# RS9113-XXX-X1X_Breakout.net
KiCad netlist of a schematic drawn in EAGLE
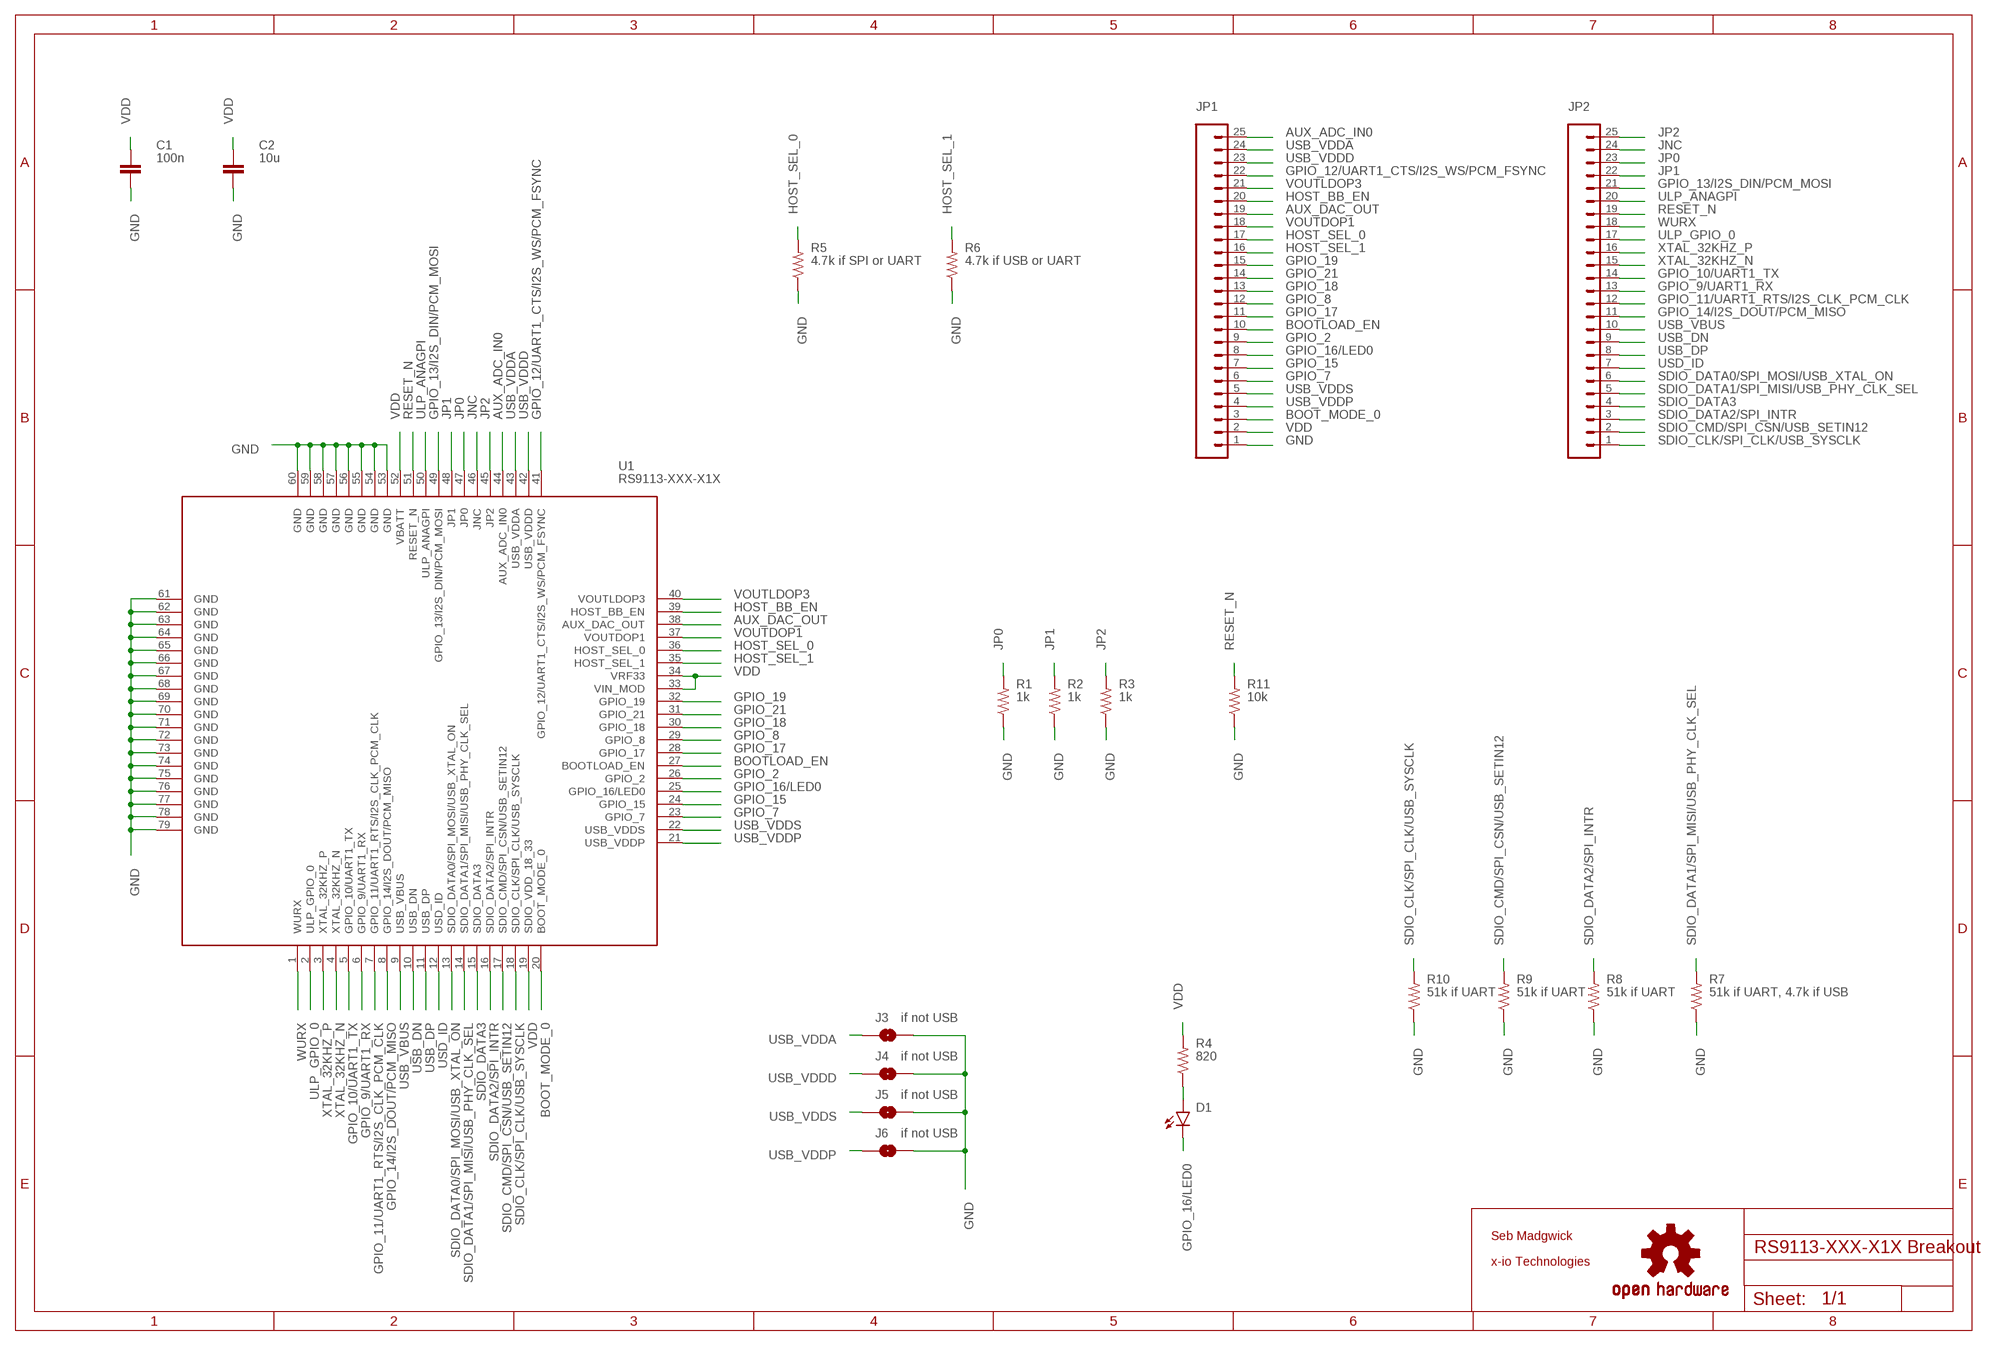
[diagram p0: schematic, sheet 1]

(export (version "E")
  (design (tool "Eeschema 10.0.6"))
  (components
    (comp (ref "C1")
      (value "100n")
      (footprint "eagle-import:0603-CAP")
      (libsource (lib "eagle-import") (part "CAP0603-CAP"))
    )
    (comp (ref "C2")
      (value "10u")
      (footprint "eagle-import:0603-CAP")
      (libsource (lib "eagle-import") (part "CAP0603-CAP"))
    )
    (comp (ref "D1")
      (value "GREEN")
      (footprint "eagle-import:LED-0603")
      (libsource (lib "eagle-import") (part "LED-GREEN0603"))
    )
    (comp (ref "J3")
      (value "if not USB")
      (footprint "eagle-import:SJ_2S-NO")
      (libsource (lib "eagle-import") (part "SOLDERJUMPERNO"))
    )
    (comp (ref "J4")
      (value "if not USB")
      (footprint "eagle-import:SJ_2S-NO")
      (libsource (lib "eagle-import") (part "SOLDERJUMPERNO"))
    )
    (comp (ref "J5")
      (value "if not USB")
      (footprint "eagle-import:SJ_2S-NO")
      (libsource (lib "eagle-import") (part "SOLDERJUMPERNO"))
    )
    (comp (ref "J6")
      (value "if not USB")
      (footprint "eagle-import:SJ_2S-NO")
      (libsource (lib "eagle-import") (part "SOLDERJUMPERNO"))
    )
    (comp (ref "JP1")
      (value "M25PTH")
      (footprint "eagle-import:1X25")
      (libsource (lib "eagle-import") (part "M25PTH"))
    )
    (comp (ref "JP2")
      (value "M25PTH")
      (footprint "eagle-import:1X25")
      (libsource (lib "eagle-import") (part "M25PTH"))
    )
    (comp (ref "LOGO1")
      (value "OSHW-LOGOS")
      (footprint "eagle-import:OSHW-LOGO-S")
      (libsource (lib "eagle-import") (part "OSHW-LOGOS"))
    )
    (comp (ref "R1")
      (value "1k")
      (footprint "eagle-import:0603-RES")
      (libsource (lib "eagle-import") (part "RESISTOR0603"))
    )
    (comp (ref "R2")
      (value "1k")
      (footprint "eagle-import:0603-RES")
      (libsource (lib "eagle-import") (part "RESISTOR0603"))
    )
    (comp (ref "R3")
      (value "1k")
      (footprint "eagle-import:0603-RES")
      (libsource (lib "eagle-import") (part "RESISTOR0603"))
    )
    (comp (ref "R4")
      (value "820")
      (footprint "eagle-import:0603-RES")
      (libsource (lib "eagle-import") (part "RESISTOR0603"))
    )
    (comp (ref "R5")
      (value "4.7k if SPI or UART")
      (footprint "eagle-import:0603-RES")
      (libsource (lib "eagle-import") (part "RESISTOR0603"))
    )
    (comp (ref "R6")
      (value "4.7k if USB or UART")
      (footprint "eagle-import:0603-RES")
      (libsource (lib "eagle-import") (part "RESISTOR0603"))
    )
    (comp (ref "R7")
      (value "51k if UART, 4.7k if USB")
      (footprint "eagle-import:0603-RES")
      (libsource (lib "eagle-import") (part "RESISTOR0603"))
    )
    (comp (ref "R8")
      (value "51k if UART")
      (footprint "eagle-import:0603-RES")
      (libsource (lib "eagle-import") (part "RESISTOR0603"))
    )
    (comp (ref "R9")
      (value "51k if UART")
      (footprint "eagle-import:0603-RES")
      (libsource (lib "eagle-import") (part "RESISTOR0603"))
    )
    (comp (ref "R10")
      (value "51k if UART")
      (footprint "eagle-import:0603-RES")
      (libsource (lib "eagle-import") (part "RESISTOR0603"))
    )
    (comp (ref "R11")
      (value "10k")
      (footprint "eagle-import:0603-RES")
      (libsource (lib "eagle-import") (part "RESISTOR0603"))
    )
    (comp (ref "U1")
      (value "RS9113-XXX-X1X")
      (footprint "eagle-import:RS9113-XXX-X1X")
      (libsource (lib "eagle-import") (part "RS9113-XXX-X1X"))
    )
  )
  (nets
    (net (code "1") (name "/AUX_ADC_IN0") (class "Default")
      (node (ref "JP1") (pin "25") (pinfunction "25_25") (pintype "passive"))
      (node (ref "U1") (pin "44") (pinfunction "AUX_ADC_IN0_44") (pintype "bidirectional"))
    )
    (net (code "2") (name "/AUX_DAC_OUT") (class "Default")
      (node (ref "JP1") (pin "19") (pinfunction "19_19") (pintype "passive"))
      (node (ref "U1") (pin "38") (pinfunction "AUX_DAC_OUT_38") (pintype "bidirectional"))
    )
    (net (code "3") (name "/BOOTLOAD_EN") (class "Default")
      (node (ref "JP1") (pin "10") (pinfunction "10_10") (pintype "passive"))
      (node (ref "U1") (pin "27") (pinfunction "BOOTLOAD_EN_27") (pintype "bidirectional"))
    )
    (net (code "4") (name "/BOOT_MODE_0") (class "Default")
      (node (ref "JP1") (pin "3") (pinfunction "3_3") (pintype "passive"))
      (node (ref "U1") (pin "20") (pinfunction "BOOT_MODE_0_20") (pintype "bidirectional"))
    )
    (net (code "5") (name "/GND") (class "Default")
      (node (ref "C1") (pin "2") (pinfunction "2_2") (pintype "passive"))
      (node (ref "C2") (pin "2") (pinfunction "2_2") (pintype "passive"))
      (node (ref "J3") (pin "1") (pinfunction "1_1") (pintype "passive"))
      (node (ref "J4") (pin "1") (pinfunction "1_1") (pintype "passive"))
      (node (ref "J5") (pin "1") (pinfunction "1_1") (pintype "passive"))
      (node (ref "J6") (pin "1") (pinfunction "1_1") (pintype "passive"))
      (node (ref "JP1") (pin "1") (pinfunction "1_1") (pintype "passive"))
      (node (ref "R1") (pin "1") (pinfunction "1_1") (pintype "passive"))
      (node (ref "R10") (pin "1") (pinfunction "1_1") (pintype "passive"))
      (node (ref "R11") (pin "1") (pinfunction "1_1") (pintype "passive"))
      (node (ref "R2") (pin "1") (pinfunction "1_1") (pintype "passive"))
      (node (ref "R3") (pin "1") (pinfunction "1_1") (pintype "passive"))
      (node (ref "R5") (pin "1") (pinfunction "1_1") (pintype "passive"))
      (node (ref "R6") (pin "1") (pinfunction "1_1") (pintype "passive"))
      (node (ref "R7") (pin "1") (pinfunction "1_1") (pintype "passive"))
      (node (ref "R8") (pin "1") (pinfunction "1_1") (pintype "passive"))
      (node (ref "R9") (pin "1") (pinfunction "1_1") (pintype "passive"))
      (node (ref "U1") (pin "53") (pinfunction "GND_53") (pintype "bidirectional"))
      (node (ref "U1") (pin "54") (pinfunction "GND_54") (pintype "bidirectional"))
      (node (ref "U1") (pin "55") (pinfunction "GND_55") (pintype "bidirectional"))
      (node (ref "U1") (pin "56") (pinfunction "GND_56") (pintype "bidirectional"))
      (node (ref "U1") (pin "57") (pinfunction "GND_57") (pintype "bidirectional"))
      (node (ref "U1") (pin "58") (pinfunction "GND_58") (pintype "bidirectional"))
      (node (ref "U1") (pin "59") (pinfunction "GND_59") (pintype "bidirectional"))
      (node (ref "U1") (pin "60") (pinfunction "GND_60") (pintype "bidirectional"))
      (node (ref "U1") (pin "61") (pinfunction "GND_61") (pintype "bidirectional"))
      (node (ref "U1") (pin "62") (pinfunction "GND_62") (pintype "bidirectional"))
      (node (ref "U1") (pin "63") (pinfunction "GND_63") (pintype "bidirectional"))
      (node (ref "U1") (pin "64") (pinfunction "GND_64") (pintype "bidirectional"))
      (node (ref "U1") (pin "65") (pinfunction "GND_65") (pintype "bidirectional"))
      (node (ref "U1") (pin "66") (pinfunction "GND_66") (pintype "bidirectional"))
      (node (ref "U1") (pin "67") (pinfunction "GND_67") (pintype "bidirectional"))
      (node (ref "U1") (pin "68") (pinfunction "GND_68") (pintype "bidirectional"))
      (node (ref "U1") (pin "69") (pinfunction "GND_69") (pintype "bidirectional"))
      (node (ref "U1") (pin "70") (pinfunction "GND_70") (pintype "bidirectional"))
      (node (ref "U1") (pin "71") (pinfunction "GND_71") (pintype "bidirectional"))
      (node (ref "U1") (pin "72") (pinfunction "GND_72") (pintype "bidirectional"))
      (node (ref "U1") (pin "73") (pinfunction "GND_73") (pintype "bidirectional"))
      (node (ref "U1") (pin "74") (pinfunction "GND_74") (pintype "bidirectional"))
      (node (ref "U1") (pin "75") (pinfunction "GND_75") (pintype "bidirectional"))
      (node (ref "U1") (pin "76") (pinfunction "GND_76") (pintype "bidirectional"))
      (node (ref "U1") (pin "77") (pinfunction "GND_77") (pintype "bidirectional"))
      (node (ref "U1") (pin "78") (pinfunction "GND_78") (pintype "bidirectional"))
      (node (ref "U1") (pin "79") (pinfunction "GND_79") (pintype "bidirectional"))
    )
    (net (code "6") (name "/GPIO_2") (class "Default")
      (node (ref "JP1") (pin "9") (pinfunction "9_9") (pintype "passive"))
      (node (ref "U1") (pin "26") (pinfunction "GPIO_2_26") (pintype "bidirectional"))
    )
    (net (code "7") (name "/GPIO_7") (class "Default")
      (node (ref "JP1") (pin "6") (pinfunction "6_6") (pintype "passive"))
      (node (ref "U1") (pin "23") (pinfunction "GPIO_7_23") (pintype "bidirectional"))
    )
    (net (code "8") (name "/GPIO_8") (class "Default")
      (node (ref "JP1") (pin "12") (pinfunction "12_12") (pintype "passive"))
      (node (ref "U1") (pin "29") (pinfunction "GPIO_8_29") (pintype "bidirectional"))
    )
    (net (code "9") (name "/GPIO_9{slash}UART1_RX") (class "Default")
      (node (ref "JP2") (pin "13") (pinfunction "13_13") (pintype "passive"))
      (node (ref "U1") (pin "6") (pinfunction "GPIO_9/UART1_RX_6") (pintype "bidirectional"))
    )
    (net (code "10") (name "/GPIO_10{slash}UART1_TX") (class "Default")
      (node (ref "JP2") (pin "14") (pinfunction "14_14") (pintype "passive"))
      (node (ref "U1") (pin "5") (pinfunction "GPIO_10/UART1_TX_5") (pintype "bidirectional"))
    )
    (net (code "11") (name "/GPIO_11{slash}UART1_RTS{slash}I2S_CLK_PCM_CLK") (class "Default")
      (node (ref "JP2") (pin "12") (pinfunction "12_12") (pintype "passive"))
      (node (ref "U1") (pin "7") (pinfunction "GPIO_11/UART1_RTS/I2S_CLK_PCM_CLK_7") (pintype "bidirectional"))
    )
    (net (code "12") (name "/GPIO_12{slash}UART1_CTS{slash}I2S_WS{slash}PCM_FSYNC") (class "Default")
      (node (ref "JP1") (pin "22") (pinfunction "22_22") (pintype "passive"))
      (node (ref "U1") (pin "41") (pinfunction "GPIO_12/UART1_CTS/I2S_WS/PCM_FSYNC_41") (pintype "bidirectional"))
    )
    (net (code "13") (name "/GPIO_13{slash}I2S_DIN{slash}PCM_MOSI") (class "Default")
      (node (ref "JP2") (pin "21") (pinfunction "21_21") (pintype "passive"))
      (node (ref "U1") (pin "49") (pinfunction "GPIO_13/I2S_DIN/PCM_MOSI_49") (pintype "bidirectional"))
    )
    (net (code "14") (name "/GPIO_14{slash}I2S_DOUT{slash}PCM_MISO") (class "Default")
      (node (ref "JP2") (pin "11") (pinfunction "11_11") (pintype "passive"))
      (node (ref "U1") (pin "8") (pinfunction "GPIO_14/I2S_DOUT/PCM_MISO_8") (pintype "bidirectional"))
    )
    (net (code "15") (name "/GPIO_15") (class "Default")
      (node (ref "JP1") (pin "7") (pinfunction "7_7") (pintype "passive"))
      (node (ref "U1") (pin "24") (pinfunction "GPIO_15_24") (pintype "bidirectional"))
    )
    (net (code "16") (name "/GPIO_16{slash}LED0") (class "Default")
      (node (ref "D1") (pin "C") (pinfunction "C_C") (pintype "passive"))
      (node (ref "JP1") (pin "8") (pinfunction "8_8") (pintype "passive"))
      (node (ref "U1") (pin "25") (pinfunction "GPIO_16/LED0_25") (pintype "bidirectional"))
    )
    (net (code "17") (name "/GPIO_17") (class "Default")
      (node (ref "JP1") (pin "11") (pinfunction "11_11") (pintype "passive"))
      (node (ref "U1") (pin "28") (pinfunction "GPIO_17_28") (pintype "bidirectional"))
    )
    (net (code "18") (name "/GPIO_18") (class "Default")
      (node (ref "JP1") (pin "13") (pinfunction "13_13") (pintype "passive"))
      (node (ref "U1") (pin "30") (pinfunction "GPIO_18_30") (pintype "bidirectional"))
    )
    (net (code "19") (name "/GPIO_19") (class "Default")
      (node (ref "JP1") (pin "15") (pinfunction "15_15") (pintype "passive"))
      (node (ref "U1") (pin "32") (pinfunction "GPIO_19_32") (pintype "bidirectional"))
    )
    (net (code "20") (name "/GPIO_21") (class "Default")
      (node (ref "JP1") (pin "14") (pinfunction "14_14") (pintype "passive"))
      (node (ref "U1") (pin "31") (pinfunction "GPIO_21_31") (pintype "bidirectional"))
    )
    (net (code "21") (name "/HOST_BB_EN") (class "Default")
      (node (ref "JP1") (pin "20") (pinfunction "20_20") (pintype "passive"))
      (node (ref "U1") (pin "39") (pinfunction "HOST_BB_EN_39") (pintype "bidirectional"))
    )
    (net (code "22") (name "/HOST_SEL_0") (class "Default")
      (node (ref "JP1") (pin "17") (pinfunction "17_17") (pintype "passive"))
      (node (ref "R5") (pin "2") (pinfunction "2_2") (pintype "passive"))
      (node (ref "U1") (pin "36") (pinfunction "HOST_SEL_0_36") (pintype "bidirectional"))
    )
    (net (code "23") (name "/HOST_SEL_1") (class "Default")
      (node (ref "JP1") (pin "16") (pinfunction "16_16") (pintype "passive"))
      (node (ref "R6") (pin "2") (pinfunction "2_2") (pintype "passive"))
      (node (ref "U1") (pin "35") (pinfunction "HOST_SEL_1_35") (pintype "bidirectional"))
    )
    (net (code "24") (name "/JNC") (class "Default")
      (node (ref "JP2") (pin "24") (pinfunction "24_24") (pintype "passive"))
      (node (ref "U1") (pin "46") (pinfunction "JNC_46") (pintype "bidirectional"))
    )
    (net (code "25") (name "/JP0") (class "Default")
      (node (ref "JP2") (pin "23") (pinfunction "23_23") (pintype "passive"))
      (node (ref "R1") (pin "2") (pinfunction "2_2") (pintype "passive"))
      (node (ref "U1") (pin "47") (pinfunction "JP0_47") (pintype "bidirectional"))
    )
    (net (code "26") (name "/JP1") (class "Default")
      (node (ref "JP2") (pin "22") (pinfunction "22_22") (pintype "passive"))
      (node (ref "R2") (pin "2") (pinfunction "2_2") (pintype "passive"))
      (node (ref "U1") (pin "48") (pinfunction "JP1_48") (pintype "bidirectional"))
    )
    (net (code "27") (name "/JP2") (class "Default")
      (node (ref "JP2") (pin "25") (pinfunction "25_25") (pintype "passive"))
      (node (ref "R3") (pin "2") (pinfunction "2_2") (pintype "passive"))
      (node (ref "U1") (pin "45") (pinfunction "JP2_45") (pintype "bidirectional"))
    )
    (net (code "28") (name "/RESET_N") (class "Default")
      (node (ref "JP2") (pin "19") (pinfunction "19_19") (pintype "passive"))
      (node (ref "R11") (pin "2") (pinfunction "2_2") (pintype "passive"))
      (node (ref "U1") (pin "51") (pinfunction "RESET_N_51") (pintype "bidirectional"))
    )
    (net (code "29") (name "/SDIO_CLK{slash}SPI_CLK{slash}USB_SYSCLK") (class "Default")
      (node (ref "JP2") (pin "1") (pinfunction "1_1") (pintype "passive"))
      (node (ref "R10") (pin "2") (pinfunction "2_2") (pintype "passive"))
      (node (ref "U1") (pin "18") (pinfunction "SDIO_CLK/SPI_CLK/USB_SYSCLK_18") (pintype "bidirectional"))
    )
    (net (code "30") (name "/SDIO_CMD{slash}SPI_CSN{slash}USB_SETIN12") (class "Default")
      (node (ref "JP2") (pin "2") (pinfunction "2_2") (pintype "passive"))
      (node (ref "R9") (pin "2") (pinfunction "2_2") (pintype "passive"))
      (node (ref "U1") (pin "17") (pinfunction "SDIO_CMD/SPI_CSN/USB_SETIN12_17") (pintype "bidirectional"))
    )
    (net (code "31") (name "/SDIO_DATA0{slash}SPI_MOSI{slash}USB_XTAL_ON") (class "Default")
      (node (ref "JP2") (pin "6") (pinfunction "6_6") (pintype "passive"))
      (node (ref "U1") (pin "13") (pinfunction "SDIO_DATA0/SPI_MOSI/USB_XTAL_ON_13") (pintype "bidirectional"))
    )
    (net (code "32") (name "/SDIO_DATA1{slash}SPI_MISI{slash}USB_PHY_CLK_SEL") (class "Default")
      (node (ref "JP2") (pin "5") (pinfunction "5_5") (pintype "passive"))
      (node (ref "R7") (pin "2") (pinfunction "2_2") (pintype "passive"))
      (node (ref "U1") (pin "14") (pinfunction "SDIO_DATA1/SPI_MISI/USB_PHY_CLK_SEL_14") (pintype "bidirectional"))
    )
    (net (code "33") (name "/SDIO_DATA2{slash}SPI_INTR") (class "Default")
      (node (ref "JP2") (pin "3") (pinfunction "3_3") (pintype "passive"))
      (node (ref "R8") (pin "2") (pinfunction "2_2") (pintype "passive"))
      (node (ref "U1") (pin "16") (pinfunction "SDIO_DATA2/SPI_INTR_16") (pintype "bidirectional"))
    )
    (net (code "34") (name "/SDIO_DATA3") (class "Default")
      (node (ref "JP2") (pin "4") (pinfunction "4_4") (pintype "passive"))
      (node (ref "U1") (pin "15") (pinfunction "SDIO_DATA3_15") (pintype "bidirectional"))
    )
    (net (code "35") (name "/ULP_ANAGPI") (class "Default")
      (node (ref "JP2") (pin "20") (pinfunction "20_20") (pintype "passive"))
      (node (ref "U1") (pin "50") (pinfunction "ULP_ANAGPI_50") (pintype "bidirectional"))
    )
    (net (code "36") (name "/ULP_GPIO_0") (class "Default")
      (node (ref "JP2") (pin "17") (pinfunction "17_17") (pintype "passive"))
      (node (ref "U1") (pin "2") (pinfunction "ULP_GPIO_0_2") (pintype "bidirectional"))
    )
    (net (code "37") (name "/USB_DN") (class "Default")
      (node (ref "JP2") (pin "9") (pinfunction "9_9") (pintype "passive"))
      (node (ref "U1") (pin "10") (pinfunction "USB_DN_10") (pintype "bidirectional"))
    )
    (net (code "38") (name "/USB_DP") (class "Default")
      (node (ref "JP2") (pin "8") (pinfunction "8_8") (pintype "passive"))
      (node (ref "U1") (pin "11") (pinfunction "USB_DP_11") (pintype "bidirectional"))
    )
    (net (code "39") (name "/USB_VBUS") (class "Default")
      (node (ref "JP2") (pin "10") (pinfunction "10_10") (pintype "passive"))
      (node (ref "U1") (pin "9") (pinfunction "USB_VBUS_9") (pintype "bidirectional"))
    )
    (net (code "40") (name "/USB_VDDA") (class "Default")
      (node (ref "J3") (pin "2") (pinfunction "2_2") (pintype "passive"))
      (node (ref "JP1") (pin "24") (pinfunction "24_24") (pintype "passive"))
      (node (ref "U1") (pin "43") (pinfunction "USB_VDDA_43") (pintype "bidirectional"))
    )
    (net (code "41") (name "/USB_VDDD") (class "Default")
      (node (ref "J4") (pin "2") (pinfunction "2_2") (pintype "passive"))
      (node (ref "JP1") (pin "23") (pinfunction "23_23") (pintype "passive"))
      (node (ref "U1") (pin "42") (pinfunction "USB_VDDD_42") (pintype "bidirectional"))
    )
    (net (code "42") (name "/USB_VDDP") (class "Default")
      (node (ref "J6") (pin "2") (pinfunction "2_2") (pintype "passive"))
      (node (ref "JP1") (pin "4") (pinfunction "4_4") (pintype "passive"))
      (node (ref "U1") (pin "21") (pinfunction "USB_VDDP_21") (pintype "bidirectional"))
    )
    (net (code "43") (name "/USB_VDDS") (class "Default")
      (node (ref "J5") (pin "2") (pinfunction "2_2") (pintype "passive"))
      (node (ref "JP1") (pin "5") (pinfunction "5_5") (pintype "passive"))
      (node (ref "U1") (pin "22") (pinfunction "USB_VDDS_22") (pintype "bidirectional"))
    )
    (net (code "44") (name "/USD_ID") (class "Default")
      (node (ref "JP2") (pin "7") (pinfunction "7_7") (pintype "passive"))
      (node (ref "U1") (pin "12") (pinfunction "USD_ID_12") (pintype "bidirectional"))
    )
    (net (code "45") (name "/VDD") (class "Default")
      (node (ref "C1") (pin "1") (pinfunction "1_1") (pintype "passive"))
      (node (ref "C2") (pin "1") (pinfunction "1_1") (pintype "passive"))
      (node (ref "JP1") (pin "2") (pinfunction "2_2") (pintype "passive"))
      (node (ref "R4") (pin "2") (pinfunction "2_2") (pintype "passive"))
      (node (ref "U1") (pin "19") (pinfunction "SDIO_VDD_18_33_19") (pintype "bidirectional"))
      (node (ref "U1") (pin "33") (pinfunction "VIN_MOD_33") (pintype "bidirectional"))
      (node (ref "U1") (pin "34") (pinfunction "VRF33_34") (pintype "bidirectional"))
      (node (ref "U1") (pin "52") (pinfunction "VBATT_52") (pintype "bidirectional"))
    )
    (net (code "46") (name "/VOUTDOP1") (class "Default")
      (node (ref "JP1") (pin "18") (pinfunction "18_18") (pintype "passive"))
      (node (ref "U1") (pin "37") (pinfunction "VOUTDOP1_37") (pintype "bidirectional"))
    )
    (net (code "47") (name "/VOUTLDOP3") (class "Default")
      (node (ref "JP1") (pin "21") (pinfunction "21_21") (pintype "passive"))
      (node (ref "U1") (pin "40") (pinfunction "VOUTLDOP3_40") (pintype "bidirectional"))
    )
    (net (code "48") (name "/WURX") (class "Default")
      (node (ref "JP2") (pin "18") (pinfunction "18_18") (pintype "passive"))
      (node (ref "U1") (pin "1") (pinfunction "WURX_1") (pintype "bidirectional"))
    )
    (net (code "49") (name "/XTAL_32KHZ_N") (class "Default")
      (node (ref "JP2") (pin "15") (pinfunction "15_15") (pintype "passive"))
      (node (ref "U1") (pin "4") (pinfunction "XTAL_32KHZ_N_4") (pintype "bidirectional"))
    )
    (net (code "50") (name "/XTAL_32KHZ_P") (class "Default")
      (node (ref "JP2") (pin "16") (pinfunction "16_16") (pintype "passive"))
      (node (ref "U1") (pin "3") (pinfunction "XTAL_32KHZ_P_3") (pintype "bidirectional"))
    )
    (net (code "51") (name "Net-(D1-PadA)") (class "Default")
      (node (ref "D1") (pin "A") (pinfunction "A_A") (pintype "passive"))
      (node (ref "R4") (pin "1") (pinfunction "1_1") (pintype "passive"))
    )
  )
)
